# 03_Power.net
KiCad netlist of a schematic drawn in Altium Designer
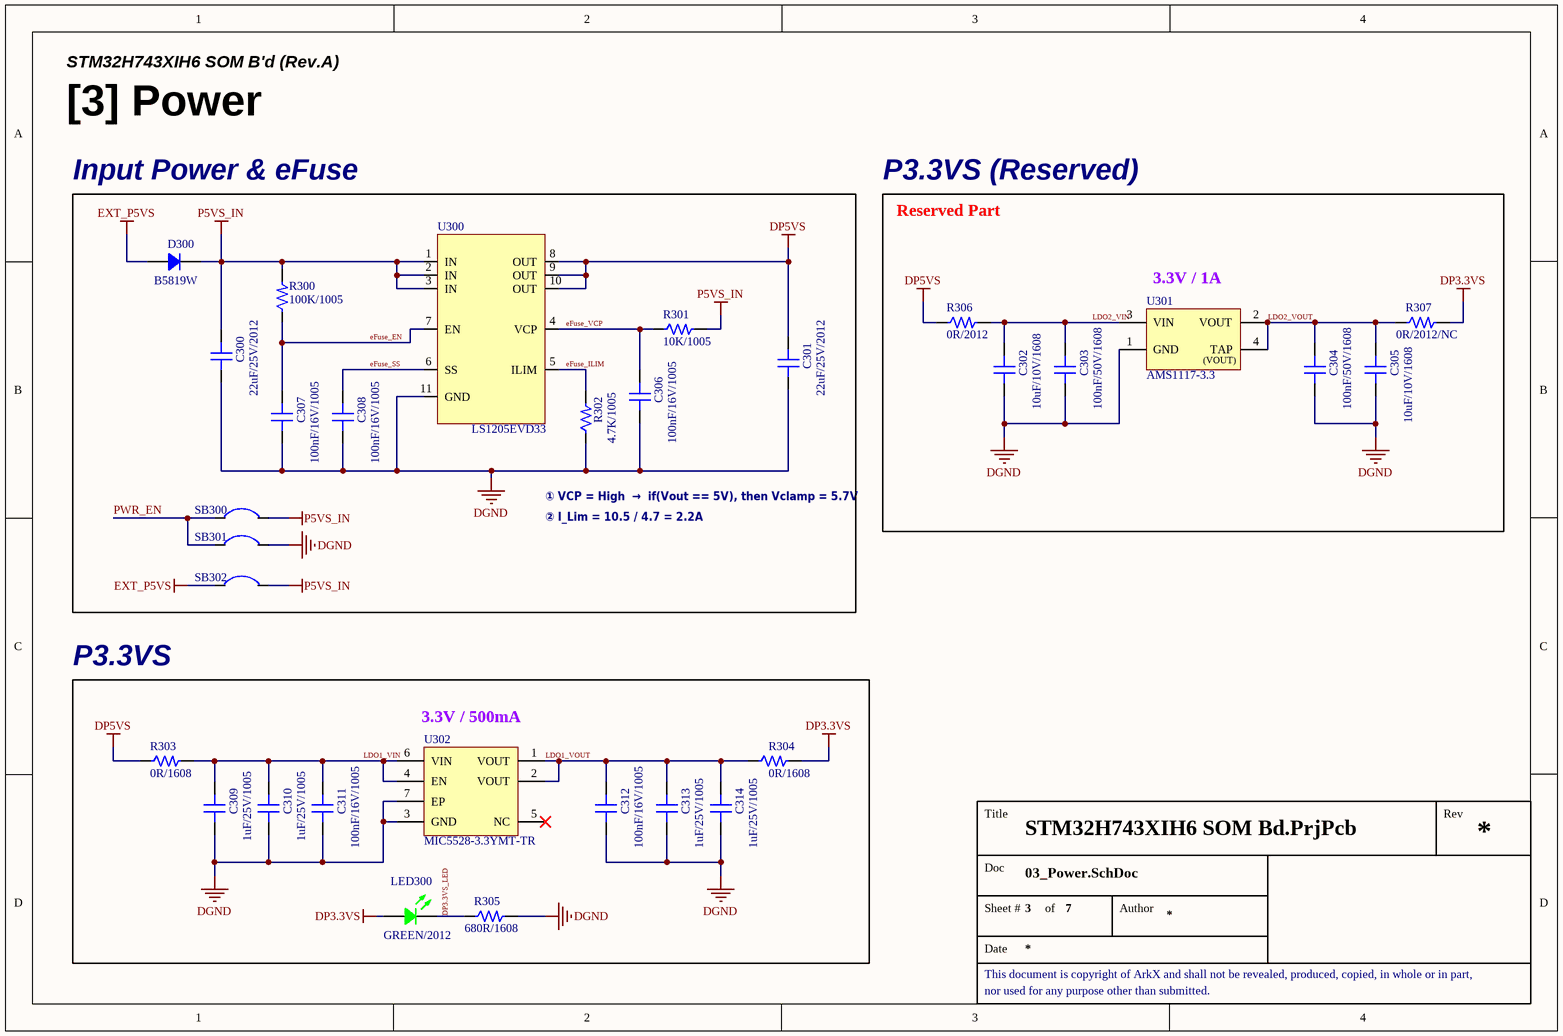
[diagram p0: 03_Power.SchDoc]

(export (version "E")
  (design (tool "Eeschema 10.0.6"))
  (components
    (comp (ref "C300")
      (value "22uF/25V/2012")
      (footprint "CAP 2012 (0805_INCH)")
      (description "Ceramic CAP_22uF/25V/2012")
      (fields (field (name "LCSC PART #") "C45783"))
      (libsource (lib "Arkx") (part "CAP_22uF/25V/2012"))
    )
    (comp (ref "C301")
      (value "22uF/25V/2012")
      (footprint "CAP 2012 (0805_INCH)")
      (description "Ceramic CAP_22uF/25V/2012")
      (fields (field (name "LCSC PART #") "C45783"))
      (libsource (lib "Arkx") (part "CAP_22uF/25V/2012"))
    )
    (comp (ref "C302")
      (value "10uF/10V/1608")
      (footprint "CAP 1608 (0603_INCH)")
      (description "Ceramic CAP_10uF/10V/1608")
      (fields (field (name "LCSC PART #") "C19702"))
      (libsource (lib "Arkx") (part "CAP_10uF/10V/1608"))
    )
    (comp (ref "C303")
      (value "100nF/50V/1608")
      (footprint "CAP 1608 (0603_INCH)")
      (description "Ceramic CAP_100nF/50V/1608")
      (fields (field (name "LCSC PART #") "C14663"))
      (libsource (lib "Arkx") (part "CAP_100nF/50V/1608"))
    )
    (comp (ref "C304")
      (value "100nF/50V/1608")
      (footprint "CAP 1608 (0603_INCH)")
      (description "Ceramic CAP_100nF/50V/1608")
      (fields (field (name "LCSC PART #") "C14663"))
      (libsource (lib "Arkx") (part "CAP_100nF/50V/1608"))
    )
    (comp (ref "C305")
      (value "10uF/10V/1608")
      (footprint "CAP 1608 (0603_INCH)")
      (description "Ceramic CAP_10uF/10V/1608")
      (fields (field (name "LCSC PART #") "C19702"))
      (libsource (lib "Arkx") (part "CAP_10uF/10V/1608"))
    )
    (comp (ref "C306")
      (value "100nF/16V/1005")
      (footprint "CAP 1005 (0402_INCH)")
      (description "Ceramic CAP_100nF/16V/1005")
      (fields (field (name "LCSC PART #") "C1525"))
      (libsource (lib "Arkx") (part "CAP_100nF/16V/1005"))
    )
    (comp (ref "C307")
      (value "100nF/16V/1005")
      (footprint "CAP 1005 (0402_INCH)")
      (description "Ceramic CAP_100nF/16V/1005")
      (fields (field (name "LCSC PART #") "C1525"))
      (libsource (lib "Arkx") (part "CAP_100nF/16V/1005"))
    )
    (comp (ref "C308")
      (value "100nF/16V/1005")
      (footprint "CAP 1005 (0402_INCH)")
      (description "Ceramic CAP_100nF/16V/1005")
      (fields (field (name "LCSC PART #") "C1525"))
      (libsource (lib "Arkx") (part "CAP_100nF/16V/1005"))
    )
    (comp (ref "C309")
      (value "1uF/25V/1005")
      (footprint "CAP 1005 (0402_INCH)")
      (description "Ceramic CAP_1uF/25V/1005")
      (fields (field (name "LCSC PART #") "C52923"))
      (libsource (lib "Arkx") (part "CAP_1uF/25V/1005"))
    )
    (comp (ref "C310")
      (value "1uF/25V/1005")
      (footprint "CAP 1005 (0402_INCH)")
      (description "Ceramic CAP_1uF/25V/1005")
      (fields (field (name "LCSC PART #") "C52923"))
      (libsource (lib "Arkx") (part "CAP_1uF/25V/1005"))
    )
    (comp (ref "C311")
      (value "100nF/16V/1005")
      (footprint "CAP 1005 (0402_INCH)")
      (description "Ceramic CAP_100nF/16V/1005")
      (fields (field (name "LCSC PART #") "C1525"))
      (libsource (lib "Arkx") (part "CAP_100nF/16V/1005"))
    )
    (comp (ref "C312")
      (value "100nF/16V/1005")
      (footprint "CAP 1005 (0402_INCH)")
      (description "Ceramic CAP_100nF/16V/1005")
      (fields (field (name "LCSC PART #") "C1525"))
      (libsource (lib "Arkx") (part "CAP_100nF/16V/1005"))
    )
    (comp (ref "C313")
      (value "1uF/25V/1005")
      (footprint "CAP 1005 (0402_INCH)")
      (description "Ceramic CAP_1uF/25V/1005")
      (fields (field (name "LCSC PART #") "C52923"))
      (libsource (lib "Arkx") (part "CAP_1uF/25V/1005"))
    )
    (comp (ref "C314")
      (value "1uF/25V/1005")
      (footprint "CAP 1005 (0402_INCH)")
      (description "Ceramic CAP_1uF/25V/1005")
      (fields (field (name "LCSC PART #") "C52923"))
      (libsource (lib "Arkx") (part "CAP_1uF/25V/1005"))
    )
    (comp (ref "D300")
      (value "B5819W")
      (footprint "DIO_SOD-123")
      (description "40V 600mV@1A 1A SOD-123  Schottky Barrier Diodes (SBD) ROHS")
      (fields (field (name "LCSC PART #") "C8598"))
      (libsource (lib "Arkx") (part "DIO_B5819W"))
    )
    (comp (ref "LED300")
      (value "GREEN/2012")
      (footprint "LED MHT170RGBCT (GREEN)")
      (fields (field (name "LCSC PART #") "C2962094"))
      (libsource (lib "Arkx") (part "LED_MHT170RGBCT(GREEN)"))
    )
    (comp (ref "R300")
      (value "100K/1005")
      (footprint "RES 1005 (0402_inch)")
      (description "RES_100K/1005/62.5mW")
      (fields (field (name "LCSC PART #") "C25741"))
      (libsource (lib "Arkx") (part "RES_100K/1005/62.5mW"))
    )
    (comp (ref "R301")
      (value "10K/1005")
      (footprint "RES 1005 (0402_inch)")
      (description "RES_10K/1005/62.5mW")
      (fields (field (name "LCSC PART #") "C25744"))
      (libsource (lib "Arkx") (part "RES_10K/1005/62.5mW"))
    )
    (comp (ref "R302")
      (value "4.7K/1005")
      (footprint "RES 1005 (0402_inch)")
      (description "RES_4.7K/1005/62.5mW")
      (fields (field (name "LCSC PART #") "C25900"))
      (libsource (lib "Arkx") (part "RES_4.7K/1005/62.5mW"))
    )
    (comp (ref "R303")
      (value "0R/1608")
      (footprint "RES 1608 (0603_inch)")
      (description "RES_0R/1608/0.1W")
      (fields (field (name "LCSC PART #") "C21189"))
      (libsource (lib "Arkx") (part "RES_0R/1608/0.1W"))
    )
    (comp (ref "R304")
      (value "0R/1608")
      (footprint "RES 1608 (0603_inch)")
      (description "RES_0R/1608/0.1W")
      (fields (field (name "LCSC PART #") "C21189"))
      (libsource (lib "Arkx") (part "RES_0R/1608/0.1W"))
    )
    (comp (ref "R305")
      (value "680R/1608")
      (footprint "RES 1608 (0603_inch)")
      (description "RES_680R/1608/0.1W")
      (fields (field (name "LCSC PART #") "C23228"))
      (libsource (lib "Arkx") (part "RES_680R/1608/0.1W"))
    )
    (comp (ref "R306")
      (value "0R/2012")
      (footprint "RES 2012 (0805_inch)")
      (description "RES_0R/2012/0.125W")
      (fields (field (name "LCSC PART #") "C17477"))
      (libsource (lib "Arkx") (part "RES_0R/2012/0.125W"))
    )
    (comp (ref "R307")
      (value "0R/2012/NC")
      (footprint "RES 2012 (0805_INCH)/NC")
      (description "0R/2012/0.125W/NC")
      (libsource (lib "Arkx") (part "RES_NC_0R/2012/0.125W"))
    )
    (comp (ref "SB300")
      (value "SB")
      (footprint "SB (Solder-Bridge)")
      (description "SB_Solder-Bridge")
      (libsource (lib "Arkx") (part "SB_Solder-Bridge"))
    )
    (comp (ref "SB301")
      (value "SB")
      (footprint "SB (Solder-Bridge)")
      (description "SB_Solder-Bridge")
      (libsource (lib "Arkx") (part "SB_Solder-Bridge"))
    )
    (comp (ref "SB302")
      (value "SB")
      (footprint "SB (Solder-Bridge)")
      (description "SB_Solder-Bridge")
      (libsource (lib "Arkx") (part "SB_Solder-Bridge"))
    )
    (comp (ref "U300")
      (value "LS1205EVD33")
      (footprint "IC_DFN_3x3_10L")
      (description "18V, 5A eFuse with Programmable Current Limit and Output Voltage Clamp, 10-DFN (3x3)")
      (libsource (lib "Arkx") (part "IC_eFUSE_LS1205EVD33"))
    )
    (comp (ref "U301")
      (value "AMS1117-3.3")
      (footprint "SOT 223-3 (DIODES INCORPORATED)")
      (fields (field (name "LCSC PART #") "C6186"))
      (libsource (lib "Arkx") (part "IC_REG_AMS1117-3.3"))
    )
    (comp (ref "U302")
      (value "MIC5528-3.3YMT-TR")
      (footprint "IC_TDFN-6")
      (description "Linear Voltage Regulator IC Positive Fixed 1 Output 500mA 6-TDFN (1.2x1.2)")
      (fields (field (name "LCSC PART #") "C622490"))
      (libsource (lib "Arkx") (part "IC_REG_MIC5528-3.3YMT-TR"))
    )
  )
  (nets
    (net (code "1") (name "/DP3.3VS_LED") (class "Default")
      (node (ref "LED300") (pin "2") (pinfunction "GREEN_2") (pintype "passive"))
      (node (ref "R305") (pin "1") (pinfunction "1_1") (pintype "passive"))
    )
    (net (code "2") (name "/LDO1_VIN") (class "Default")
      (node (ref "C309") (pin "2") (pinfunction "2_2") (pintype "passive"))
      (node (ref "C310") (pin "2") (pinfunction "2_2") (pintype "passive"))
      (node (ref "C311") (pin "2") (pinfunction "2_2") (pintype "passive"))
      (node (ref "R303") (pin "2") (pinfunction "2_2") (pintype "passive"))
      (node (ref "U302") (pin "4") (pinfunction "EN_4") (pintype "passive"))
      (node (ref "U302") (pin "6") (pinfunction "VIN_6") (pintype "passive"))
    )
    (net (code "3") (name "/LDO1_VOUT") (class "Default")
      (node (ref "C312") (pin "2") (pinfunction "2_2") (pintype "passive"))
      (node (ref "C313") (pin "2") (pinfunction "2_2") (pintype "passive"))
      (node (ref "C314") (pin "2") (pinfunction "2_2") (pintype "passive"))
      (node (ref "R304") (pin "1") (pinfunction "1_1") (pintype "passive"))
      (node (ref "U302") (pin "1") (pinfunction "VOUT_1") (pintype "passive"))
      (node (ref "U302") (pin "2") (pinfunction "VOUT_2") (pintype "passive"))
    )
    (net (code "4") (name "/LDO2_VIN") (class "Default")
      (node (ref "C302") (pin "2") (pinfunction "2_2") (pintype "passive"))
      (node (ref "C303") (pin "2") (pinfunction "2_2") (pintype "passive"))
      (node (ref "R306") (pin "2") (pinfunction "2_2") (pintype "passive"))
      (node (ref "U301") (pin "3") (pinfunction "VIN_3") (pintype "passive"))
    )
    (net (code "5") (name "/LDO2_VOUT") (class "Default")
      (node (ref "C304") (pin "2") (pinfunction "2_2") (pintype "passive"))
      (node (ref "C305") (pin "2") (pinfunction "2_2") (pintype "passive"))
      (node (ref "R307") (pin "1") (pinfunction "1_1") (pintype "passive"))
      (node (ref "U301") (pin "2") (pinfunction "VOUT_2") (pintype "passive"))
      (node (ref "U301") (pin "4") (pinfunction "TAP_4") (pintype "passive"))
    )
    (net (code "6") (name "/PWR_EN") (class "Default")
      (node (ref "SB300") (pin "1") (pinfunction "1_1") (pintype "passive"))
      (node (ref "SB301") (pin "1") (pinfunction "1_1") (pintype "passive"))
    )
    (net (code "7") (name "/eFuse_EN") (class "Default")
      (node (ref "C307") (pin "2") (pinfunction "2_2") (pintype "passive"))
      (node (ref "R300") (pin "1") (pinfunction "1_1") (pintype "passive"))
      (node (ref "U300") (pin "7") (pinfunction "EN_7") (pintype "passive"))
    )
    (net (code "8") (name "/eFuse_ILIM") (class "Default")
      (node (ref "R302") (pin "2") (pinfunction "2_2") (pintype "passive"))
      (node (ref "U300") (pin "5") (pinfunction "ILIM_5") (pintype "passive"))
    )
    (net (code "9") (name "/eFuse_SS") (class "Default")
      (node (ref "C308") (pin "2") (pinfunction "2_2") (pintype "passive"))
      (node (ref "U300") (pin "6") (pinfunction "SS_6") (pintype "passive"))
    )
    (net (code "10") (name "/eFuse_VCP") (class "Default")
      (node (ref "C306") (pin "2") (pinfunction "2_2") (pintype "passive"))
      (node (ref "R301") (pin "1") (pinfunction "1_1") (pintype "passive"))
      (node (ref "U300") (pin "4") (pinfunction "VCP_4") (pintype "passive"))
    )
    (net (code "11") (name "DGND") (class "Default")
      (node (ref "C300") (pin "1") (pinfunction "1_1") (pintype "passive"))
      (node (ref "C301") (pin "1") (pinfunction "1_1") (pintype "passive"))
      (node (ref "C302") (pin "1") (pinfunction "1_1") (pintype "passive"))
      (node (ref "C303") (pin "1") (pinfunction "1_1") (pintype "passive"))
      (node (ref "C304") (pin "1") (pinfunction "1_1") (pintype "passive"))
      (node (ref "C305") (pin "1") (pinfunction "1_1") (pintype "passive"))
      (node (ref "C306") (pin "1") (pinfunction "1_1") (pintype "passive"))
      (node (ref "C307") (pin "1") (pinfunction "1_1") (pintype "passive"))
      (node (ref "C308") (pin "1") (pinfunction "1_1") (pintype "passive"))
      (node (ref "C309") (pin "1") (pinfunction "1_1") (pintype "passive"))
      (node (ref "C310") (pin "1") (pinfunction "1_1") (pintype "passive"))
      (node (ref "C311") (pin "1") (pinfunction "1_1") (pintype "passive"))
      (node (ref "C312") (pin "1") (pinfunction "1_1") (pintype "passive"))
      (node (ref "C313") (pin "1") (pinfunction "1_1") (pintype "passive"))
      (node (ref "C314") (pin "1") (pinfunction "1_1") (pintype "passive"))
      (node (ref "R302") (pin "1") (pinfunction "1_1") (pintype "passive"))
      (node (ref "R305") (pin "2") (pinfunction "2_2") (pintype "passive"))
      (node (ref "SB301") (pin "2") (pinfunction "2_2") (pintype "passive"))
      (node (ref "U300") (pin "11") (pinfunction "GND_11") (pintype "power_in"))
      (node (ref "U301") (pin "1") (pinfunction "GND_1") (pintype "passive"))
      (node (ref "U302") (pin "3") (pinfunction "GND_3") (pintype "passive"))
      (node (ref "U302") (pin "7") (pinfunction "EP_7") (pintype "passive"))
    )
    (net (code "12") (name "DP3.3VS") (class "Default")
      (node (ref "LED300") (pin "4") (pinfunction "Common_Anode_4") (pintype "passive"))
      (node (ref "R304") (pin "2") (pinfunction "2_2") (pintype "passive"))
      (node (ref "R307") (pin "2") (pinfunction "2_2") (pintype "passive"))
    )
    (net (code "13") (name "DP5VS") (class "Default")
      (node (ref "C301") (pin "2") (pinfunction "2_2") (pintype "passive"))
      (node (ref "R303") (pin "1") (pinfunction "1_1") (pintype "passive"))
      (node (ref "R306") (pin "1") (pinfunction "1_1") (pintype "passive"))
      (node (ref "U300") (pin "10") (pinfunction "OUT_10") (pintype "power_in"))
      (node (ref "U300") (pin "8") (pinfunction "OUT_8") (pintype "power_in"))
      (node (ref "U300") (pin "9") (pinfunction "OUT_9") (pintype "power_in"))
    )
    (net (code "14") (name "EXT_P5VS") (class "Default")
      (node (ref "D300") (pin "1") (pinfunction "1_1") (pintype "passive"))
      (node (ref "SB302") (pin "1") (pinfunction "1_1") (pintype "passive"))
    )
    (net (code "15") (name "P5VS_IN") (class "Default")
      (node (ref "C300") (pin "2") (pinfunction "2_2") (pintype "passive"))
      (node (ref "D300") (pin "2") (pinfunction "2_2") (pintype "passive"))
      (node (ref "R300") (pin "2") (pinfunction "2_2") (pintype "passive"))
      (node (ref "R301") (pin "2") (pinfunction "2_2") (pintype "passive"))
      (node (ref "SB300") (pin "2") (pinfunction "2_2") (pintype "passive"))
      (node (ref "SB302") (pin "2") (pinfunction "2_2") (pintype "passive"))
      (node (ref "U300") (pin "1") (pinfunction "IN_1") (pintype "power_in"))
      (node (ref "U300") (pin "2") (pinfunction "IN_2") (pintype "power_in"))
      (node (ref "U300") (pin "3") (pinfunction "IN_3") (pintype "power_in"))
    )
    (net (code "16") (name "unconnected-(U302-NC-Pad5)") (class "Default")
      (node (ref "U302") (pin "5") (pinfunction "NC_5") (pintype "passive+no_connect"))
    )
  )
)
